# SCH_GSME_voltmeter_Arduino_ESP8266_TP405.net
KiCad netlist of a schematic drawn in EasyEDA
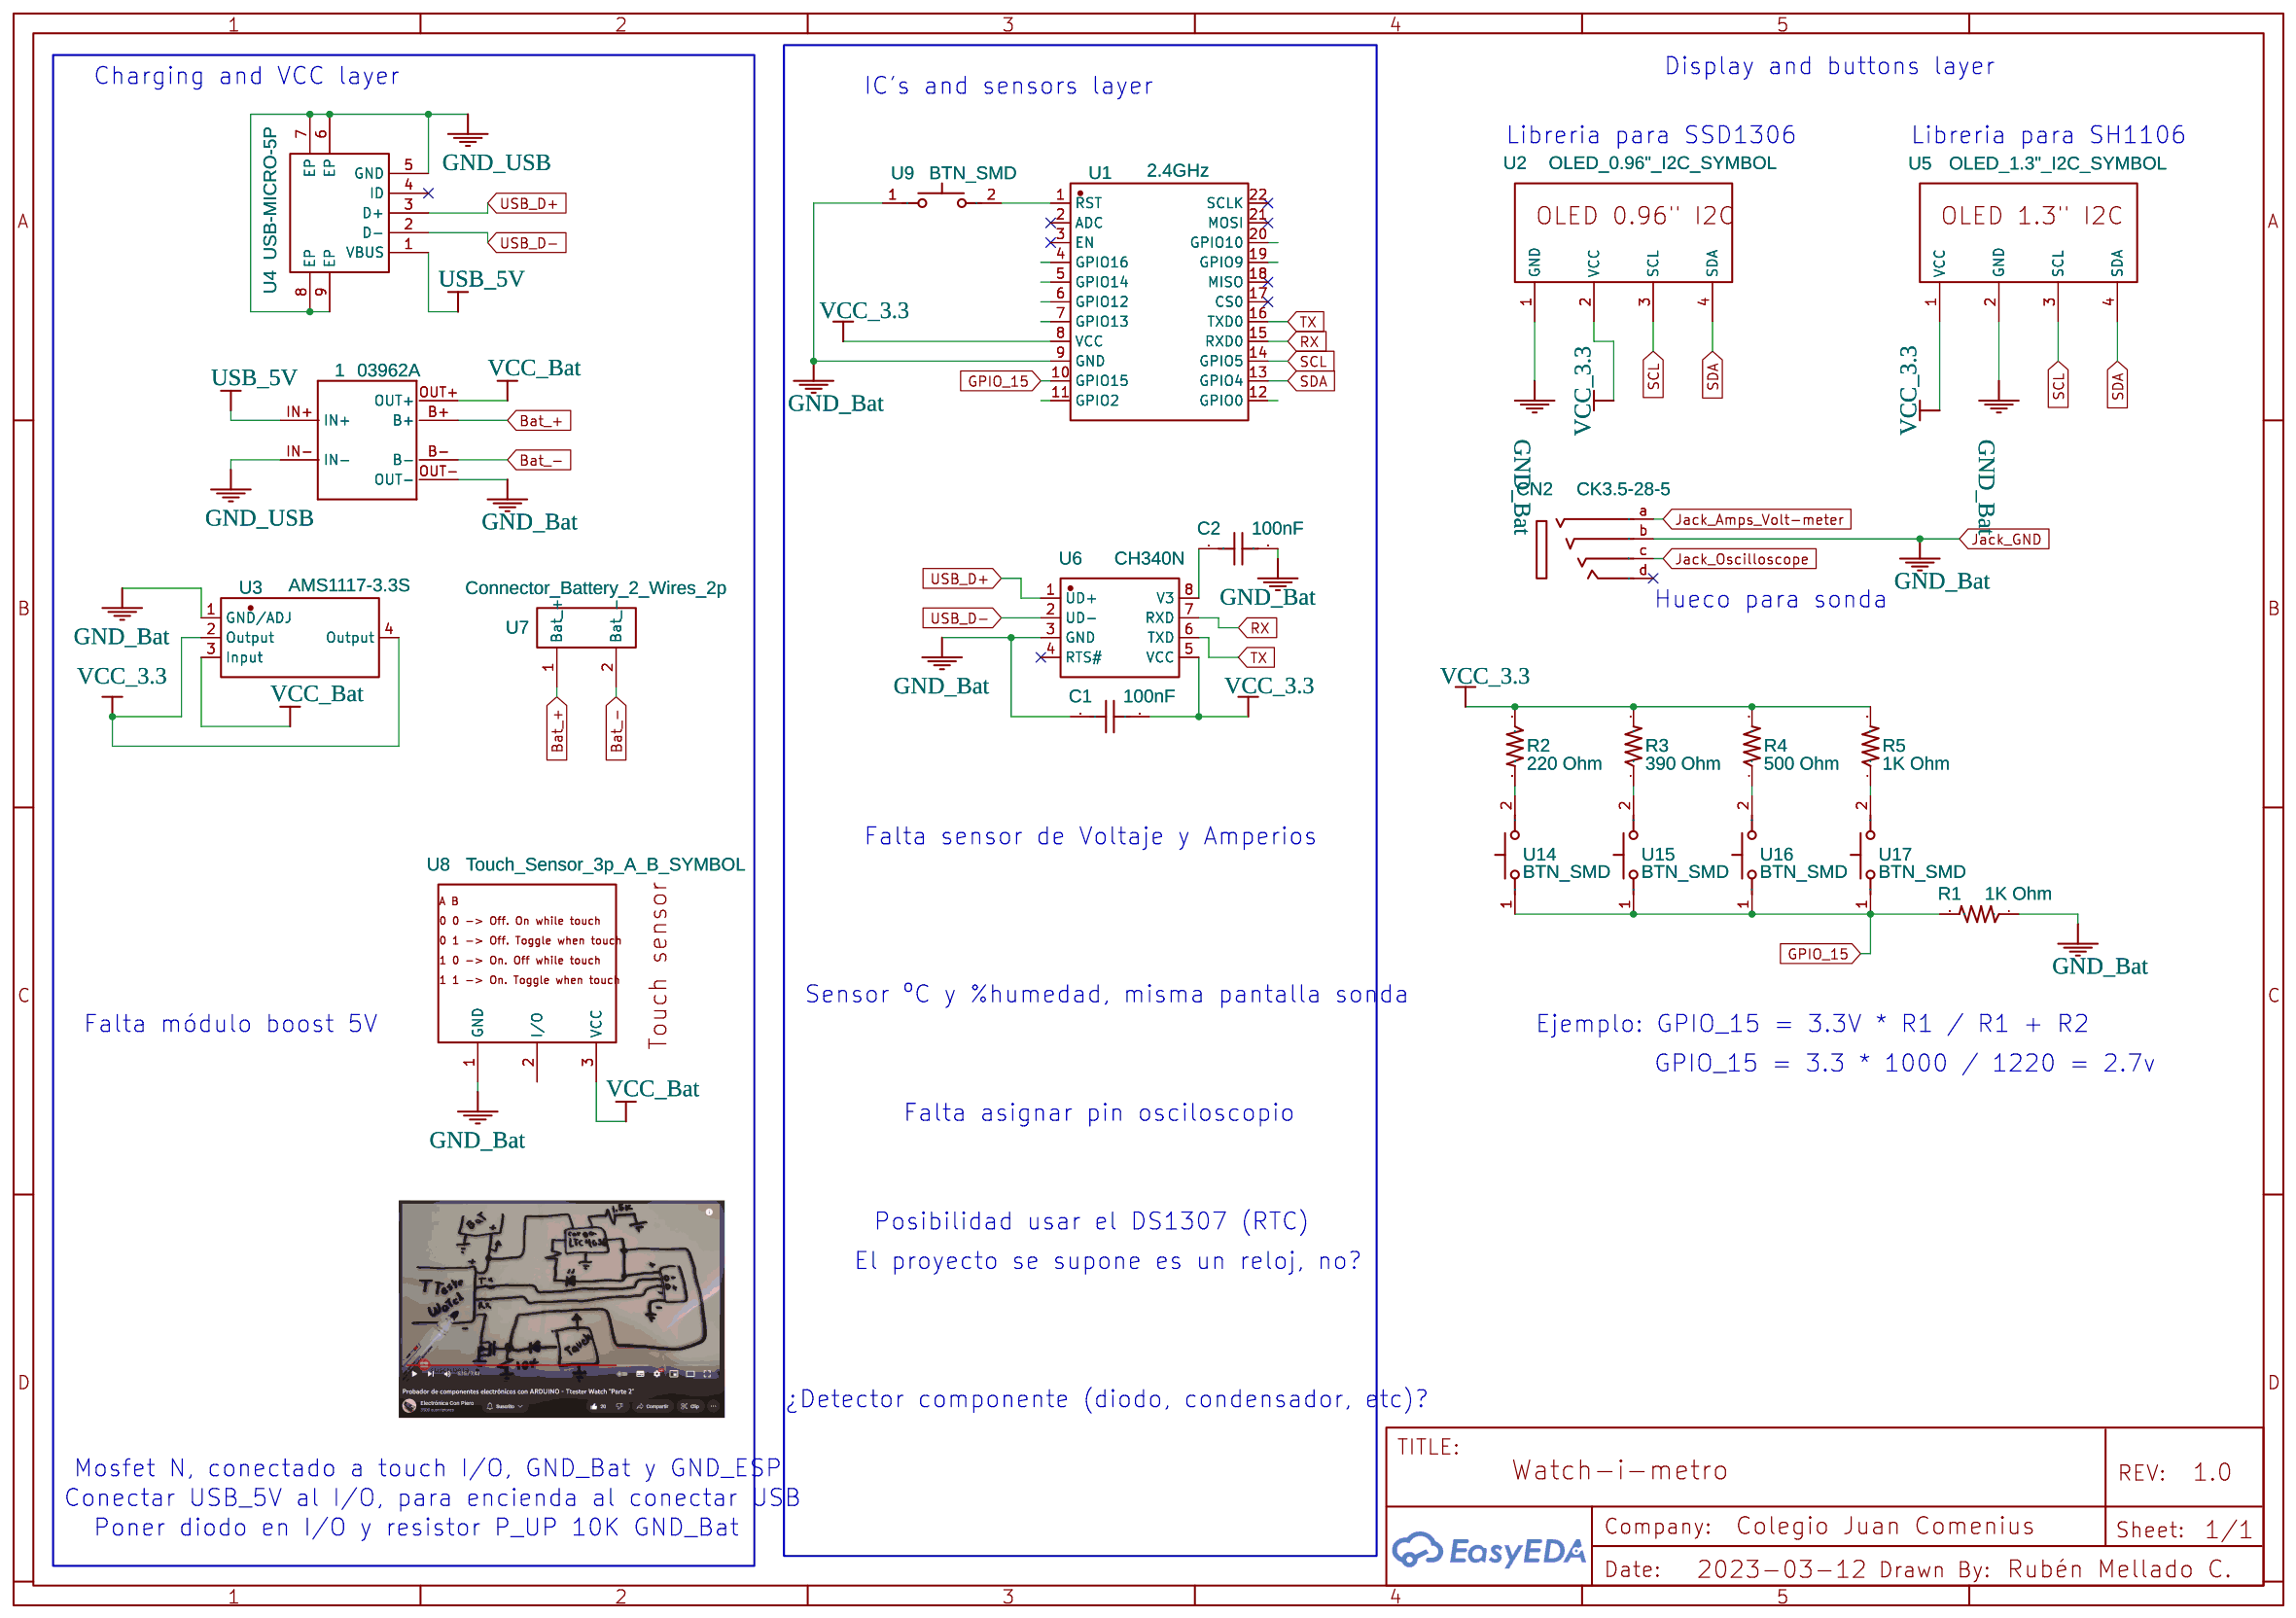
[diagram p0: schematic sheet]

(export (version "E")
  (design (tool "Eeschema 10.0.6"))
  (components
    (comp (ref "1") (value "03962A") (libsource (lib "") (part "03962A")))
    (comp (ref "C1") (value "100nF") (libsource (lib "") (part "C_0603_US")))
    (comp (ref "C2") (value "100nF") (libsource (lib "") (part "C_0603_US")))
    (comp (ref "CN2")
      (value "CK3.5-28-5")
      (fields (field (name "BOM_Supplier Part") "C718048"))
      (libsource (lib "") (part "CK3.5-28-5"))
    )
    (comp (ref "R1") (value "1K Ohm") (libsource (lib "") (part "RESISTOR0603_2")))
    (comp (ref "R2") (value "220 Ohm") (libsource (lib "") (part "RESISTOR0603_1")))
    (comp (ref "R3") (value "390 Ohm") (libsource (lib "") (part "RESISTOR0603")))
    (comp (ref "R4") (value "500 Ohm") (libsource (lib "") (part "RESISTOR0603")))
    (comp (ref "R5") (value "1K Ohm") (libsource (lib "") (part "RESISTOR0603")))
    (comp (ref "U1")
      (value "2.4GHz")
      (fields
        (field (name "BOM_Manufacturer Part") "ESP-12F(ESP8266MOD)")
        (field (name "BOM_Supplier Part") "C82891")
      )
      (libsource (lib "") (part "ESP-12F(ESP8266MOD)"))
    )
    (comp (ref "U2")
      (value "OLED_0.96\"_I2C_SYMBOL")
      (libsource (lib "") (part "OLED_0.96{dblquote}_I2C_SYMBOL"))
    )
    (comp (ref "U3")
      (value "AMS1117-3.3S")
      (fields (field (name "BOM_Supplier Part") "C2842296"))
      (libsource (lib "") (part "AMS1117-3.3S"))
    )
    (comp (ref "U4")
      (value "USB-MICRO-5P")
      (fields
        (field (name "BOM_Manufacturer Part") "USB-Micro-5P")
        (field (name "BOM_Supplier Part") "C9900014288")
      )
      (libsource (lib "") (part "USB-MICRO-5P"))
    )
    (comp (ref "U5")
      (value "OLED_1.3\"_I2C_SYMBOL")
      (libsource (lib "") (part "OLED_1.3{dblquote}_I2C_SYMBOL"))
    )
    (comp (ref "U6")
      (value "CH340N")
      (fields (field (name "BOM_Supplier Part") "C506813"))
      (libsource (lib "") (part "CH340N"))
    )
    (comp (ref "U7")
      (value "Connector_Battery_2_Wires_2p")
      (libsource (lib "") (part "Connector_Battery_2_Wires_2p"))
    )
    (comp (ref "U8")
      (value "Touch_Sensor_3p_A_B_SYMBOL")
      (libsource (lib "") (part "Touch_Sensor_3p_A_B_SYMBOL"))
    )
    (comp (ref "U9")
      (value "BTN_SMD")
      (fields
        (field (name "BOM_Manufacturer Part") "BUTTON2")
        (field (name "BOM_Supplier Part") "C9900005988")
      )
      (libsource (lib "") (part "BUTTON2_1"))
    )
    (comp (ref "U14")
      (value "BTN_SMD")
      (fields
        (field (name "BOM_Manufacturer Part") "BUTTON2")
        (field (name "BOM_Supplier Part") "C9900005988")
      )
      (libsource (lib "") (part "BUTTON2"))
    )
    (comp (ref "U15")
      (value "BTN_SMD")
      (fields
        (field (name "BOM_Manufacturer Part") "BUTTON2")
        (field (name "BOM_Supplier Part") "C9900005988")
      )
      (libsource (lib "") (part "BUTTON2"))
    )
    (comp (ref "U16")
      (value "BTN_SMD")
      (fields
        (field (name "BOM_Manufacturer Part") "BUTTON2")
        (field (name "BOM_Supplier Part") "C9900005988")
      )
      (libsource (lib "") (part "BUTTON2"))
    )
    (comp (ref "U17")
      (value "BTN_SMD")
      (fields
        (field (name "BOM_Manufacturer Part") "BUTTON2")
        (field (name "BOM_Supplier Part") "C9900005988")
      )
      (libsource (lib "") (part "BUTTON2"))
    )
  )
  (nets
    (net (code "1") (name "Bat_+") (class "Default")
      (node (ref "1") (pin "B+") (pinfunction "B+_B+") (pintype "bidirectional"))
      (node (ref "U7") (pin "1") (pinfunction "Bat_+_1") (pintype "unspecified"))
    )
    (net (code "2") (name "Bat_-") (class "Default")
      (node (ref "1") (pin "B-") (pinfunction "B-_B-") (pintype "bidirectional"))
      (node (ref "U7") (pin "2") (pinfunction "Bat_-_2") (pintype "unspecified"))
    )
    (net (code "3") (name "GND_USB") (class "Default")
      (node (ref "1") (pin "IN-") (pinfunction "IN-_IN-") (pintype "bidirectional"))
      (node (ref "U4") (pin "5") (pinfunction "GND_5") (pintype "unspecified"))
      (node (ref "U4") (pin "6") (pinfunction "EP_6") (pintype "unspecified"))
      (node (ref "U4") (pin "7") (pinfunction "EP_7") (pintype "unspecified"))
      (node (ref "U4") (pin "8") (pinfunction "EP_8") (pintype "unspecified"))
      (node (ref "U4") (pin "9") (pinfunction "EP_9") (pintype "unspecified"))
    )
    (net (code "4") (name "GPIO_15") (class "Default")
      (node (ref "R1") (pin "2") (pinfunction "2_2") (pintype "unspecified"))
      (node (ref "U1") (pin "10") (pinfunction "GPIO15_10") (pintype "unspecified"))
      (node (ref "U14") (pin "1") (pinfunction "1_1") (pintype "unspecified"))
      (node (ref "U15") (pin "1") (pinfunction "1_1") (pintype "unspecified"))
      (node (ref "U16") (pin "1") (pinfunction "1_1") (pintype "unspecified"))
      (node (ref "U17") (pin "1") (pinfunction "1_1") (pintype "unspecified"))
    )
    (net (code "5") (name "Jack_Amps_Volt-meter") (class "Default")
      (node (ref "CN2") (pin "a") (pinfunction "a_a") (pintype "unspecified"))
    )
    (net (code "6") (name "Jack_GND") (class "Default")
      (node (ref "1") (pin "OUT-") (pinfunction "OUT-_OUT-") (pintype "bidirectional"))
      (node (ref "C1") (pin "1") (pinfunction "1_1") (pintype "unspecified"))
      (node (ref "C2") (pin "2") (pinfunction "2_2") (pintype "unspecified"))
      (node (ref "CN2") (pin "b") (pinfunction "b_b") (pintype "unspecified"))
      (node (ref "R1") (pin "1") (pinfunction "1_1") (pintype "unspecified"))
      (node (ref "U1") (pin "9") (pinfunction "GND_9") (pintype "unspecified"))
      (node (ref "U2") (pin "1") (pinfunction "GND_1") (pintype "unspecified"))
      (node (ref "U3") (pin "1") (pinfunction "GND/ADJ_1") (pintype "unspecified"))
      (node (ref "U5") (pin "2") (pinfunction "GND_2") (pintype "unspecified"))
      (node (ref "U6") (pin "3") (pinfunction "GND_3") (pintype "unspecified"))
      (node (ref "U8") (pin "1") (pinfunction "GND_1") (pintype "unspecified"))
      (node (ref "U9") (pin "1") (pinfunction "1_1") (pintype "unspecified"))
    )
    (net (code "7") (name "Jack_Oscilloscope") (class "Default")
      (node (ref "CN2") (pin "c") (pinfunction "c_c") (pintype "unspecified"))
    )
    (net (code "8") (name "Net-(R2-Pad2)") (class "Default")
      (node (ref "R2") (pin "2") (pinfunction "2_2") (pintype "unspecified"))
      (node (ref "U14") (pin "2") (pinfunction "2_2") (pintype "unspecified"))
    )
    (net (code "9") (name "Net-(R3-Pad1)") (class "Default")
      (node (ref "R3") (pin "1") (pinfunction "1_1") (pintype "unspecified"))
      (node (ref "U15") (pin "2") (pinfunction "2_2") (pintype "unspecified"))
    )
    (net (code "10") (name "Net-(R4-Pad1)") (class "Default")
      (node (ref "R4") (pin "1") (pinfunction "1_1") (pintype "unspecified"))
      (node (ref "U16") (pin "2") (pinfunction "2_2") (pintype "unspecified"))
    )
    (net (code "11") (name "Net-(R5-Pad1)") (class "Default")
      (node (ref "R5") (pin "1") (pinfunction "1_1") (pintype "unspecified"))
      (node (ref "U17") (pin "2") (pinfunction "2_2") (pintype "unspecified"))
    )
    (net (code "12") (name "Net-(U1-RST)") (class "Default")
      (node (ref "U1") (pin "1") (pinfunction "RST_1") (pintype "unspecified"))
      (node (ref "U9") (pin "2") (pinfunction "2_2") (pintype "unspecified"))
    )
    (net (code "13") (name "Net-(U6-V3)") (class "Default")
      (node (ref "C2") (pin "1") (pinfunction "1_1") (pintype "unspecified"))
      (node (ref "U6") (pin "8") (pinfunction "V3_8") (pintype "unspecified"))
    )
    (net (code "14") (name "RX") (class "Default")
      (node (ref "U1") (pin "15") (pinfunction "RXD0_15") (pintype "unspecified"))
      (node (ref "U6") (pin "7") (pinfunction "RXD_7") (pintype "unspecified"))
    )
    (net (code "15") (name "SCL") (class "Default")
      (node (ref "U1") (pin "14") (pinfunction "GPIO5_14") (pintype "unspecified"))
      (node (ref "U2") (pin "3") (pinfunction "SCL_3") (pintype "unspecified"))
      (node (ref "U5") (pin "3") (pinfunction "SCL_3") (pintype "unspecified"))
    )
    (net (code "16") (name "SDA") (class "Default")
      (node (ref "U1") (pin "13") (pinfunction "GPIO4_13") (pintype "unspecified"))
      (node (ref "U2") (pin "4") (pinfunction "SDA_4") (pintype "unspecified"))
      (node (ref "U5") (pin "4") (pinfunction "SDA_4") (pintype "unspecified"))
    )
    (net (code "17") (name "TX") (class "Default")
      (node (ref "U1") (pin "16") (pinfunction "TXD0_16") (pintype "unspecified"))
      (node (ref "U6") (pin "6") (pinfunction "TXD_6") (pintype "unspecified"))
    )
    (net (code "18") (name "USB_5V") (class "Default")
      (node (ref "1") (pin "IN+") (pinfunction "IN+_IN+") (pintype "bidirectional"))
      (node (ref "U4") (pin "1") (pinfunction "VBUS_1") (pintype "unspecified"))
    )
    (net (code "19") (name "USB_D+") (class "Default")
      (node (ref "U4") (pin "3") (pinfunction "D+_3") (pintype "unspecified"))
      (node (ref "U6") (pin "1") (pinfunction "UD+_1") (pintype "unspecified"))
    )
    (net (code "20") (name "USB_D-") (class "Default")
      (node (ref "U4") (pin "2") (pinfunction "D-_2") (pintype "unspecified"))
      (node (ref "U6") (pin "2") (pinfunction "UD-_2") (pintype "unspecified"))
    )
    (net (code "21") (name "VCC_3.3") (class "Default")
      (node (ref "C1") (pin "2") (pinfunction "2_2") (pintype "unspecified"))
      (node (ref "R2") (pin "1") (pinfunction "1_1") (pintype "unspecified"))
      (node (ref "R3") (pin "2") (pinfunction "2_2") (pintype "unspecified"))
      (node (ref "R4") (pin "2") (pinfunction "2_2") (pintype "unspecified"))
      (node (ref "R5") (pin "2") (pinfunction "2_2") (pintype "unspecified"))
      (node (ref "U1") (pin "8") (pinfunction "VCC_8") (pintype "unspecified"))
      (node (ref "U2") (pin "2") (pinfunction "VCC_2") (pintype "unspecified"))
      (node (ref "U3") (pin "2") (pinfunction "Output_2") (pintype "unspecified"))
      (node (ref "U3") (pin "4") (pinfunction "Output_4") (pintype "unspecified"))
      (node (ref "U5") (pin "1") (pinfunction "VCC_1") (pintype "unspecified"))
      (node (ref "U6") (pin "5") (pinfunction "VCC_5") (pintype "unspecified"))
    )
    (net (code "22") (name "VCC_Bat") (class "Default")
      (node (ref "1") (pin "OUT+") (pinfunction "OUT+_OUT+") (pintype "bidirectional"))
      (node (ref "U3") (pin "3") (pinfunction "Input_3") (pintype "unspecified"))
      (node (ref "U8") (pin "3") (pinfunction "VCC_3") (pintype "unspecified"))
    )
    (net (code "23") (name "unconnected-(CN2-Padd)") (class "Default")
      (node (ref "CN2") (pin "d") (pinfunction "d_d") (pintype "unspecified+no_connect"))
    )
    (net (code "24") (name "unconnected-(U1-ADC-Pad2)") (class "Default")
      (node (ref "U1") (pin "2") (pinfunction "ADC_2") (pintype "unspecified+no_connect"))
    )
    (net (code "25") (name "unconnected-(U1-CS0-Pad17)") (class "Default")
      (node (ref "U1") (pin "17") (pinfunction "CS0_17") (pintype "unspecified+no_connect"))
    )
    (net (code "26") (name "unconnected-(U1-EN-Pad3)") (class "Default")
      (node (ref "U1") (pin "3") (pinfunction "EN_3") (pintype "unspecified+no_connect"))
    )
    (net (code "27") (name "unconnected-(U1-GPIO0-Pad12)") (class "Default")
      (node (ref "U1") (pin "12") (pinfunction "GPIO0_12") (pintype "unspecified"))
    )
    (net (code "28") (name "unconnected-(U1-GPIO2-Pad11)") (class "Default")
      (node (ref "U1") (pin "11") (pinfunction "GPIO2_11") (pintype "unspecified"))
    )
    (net (code "29") (name "unconnected-(U1-GPIO9-Pad19)") (class "Default")
      (node (ref "U1") (pin "19") (pinfunction "GPIO9_19") (pintype "unspecified"))
    )
    (net (code "30") (name "unconnected-(U1-GPIO10-Pad20)") (class "Default")
      (node (ref "U1") (pin "20") (pinfunction "GPIO10_20") (pintype "unspecified"))
    )
    (net (code "31") (name "unconnected-(U1-GPIO12-Pad6)") (class "Default")
      (node (ref "U1") (pin "6") (pinfunction "GPIO12_6") (pintype "unspecified"))
    )
    (net (code "32") (name "unconnected-(U1-GPIO13-Pad7)") (class "Default")
      (node (ref "U1") (pin "7") (pinfunction "GPIO13_7") (pintype "unspecified"))
    )
    (net (code "33") (name "unconnected-(U1-GPIO14-Pad5)") (class "Default")
      (node (ref "U1") (pin "5") (pinfunction "GPIO14_5") (pintype "unspecified"))
    )
    (net (code "34") (name "unconnected-(U1-GPIO16-Pad4)") (class "Default")
      (node (ref "U1") (pin "4") (pinfunction "GPIO16_4") (pintype "unspecified"))
    )
    (net (code "35") (name "unconnected-(U1-MISO-Pad18)") (class "Default")
      (node (ref "U1") (pin "18") (pinfunction "MISO_18") (pintype "unspecified+no_connect"))
    )
    (net (code "36") (name "unconnected-(U1-MOSI-Pad21)") (class "Default")
      (node (ref "U1") (pin "21") (pinfunction "MOSI_21") (pintype "unspecified+no_connect"))
    )
    (net (code "37") (name "unconnected-(U1-SCLK-Pad22)") (class "Default")
      (node (ref "U1") (pin "22") (pinfunction "SCLK_22") (pintype "unspecified+no_connect"))
    )
    (net (code "38") (name "unconnected-(U4-ID-Pad4)") (class "Default")
      (node (ref "U4") (pin "4") (pinfunction "ID_4") (pintype "unspecified+no_connect"))
    )
    (net (code "39") (name "unconnected-(U6-RTS#-Pad4)") (class "Default")
      (node (ref "U6") (pin "4") (pinfunction "RTS#_4") (pintype "unspecified+no_connect"))
    )
    (net (code "40") (name "unconnected-(U8-I{slash}O-Pad2)") (class "Default")
      (node (ref "U8") (pin "2") (pinfunction "I/O_2") (pintype "unspecified"))
    )
  )
)
